# arksigner1.net
KiCad netlist of a schematic drawn in Altium Designer
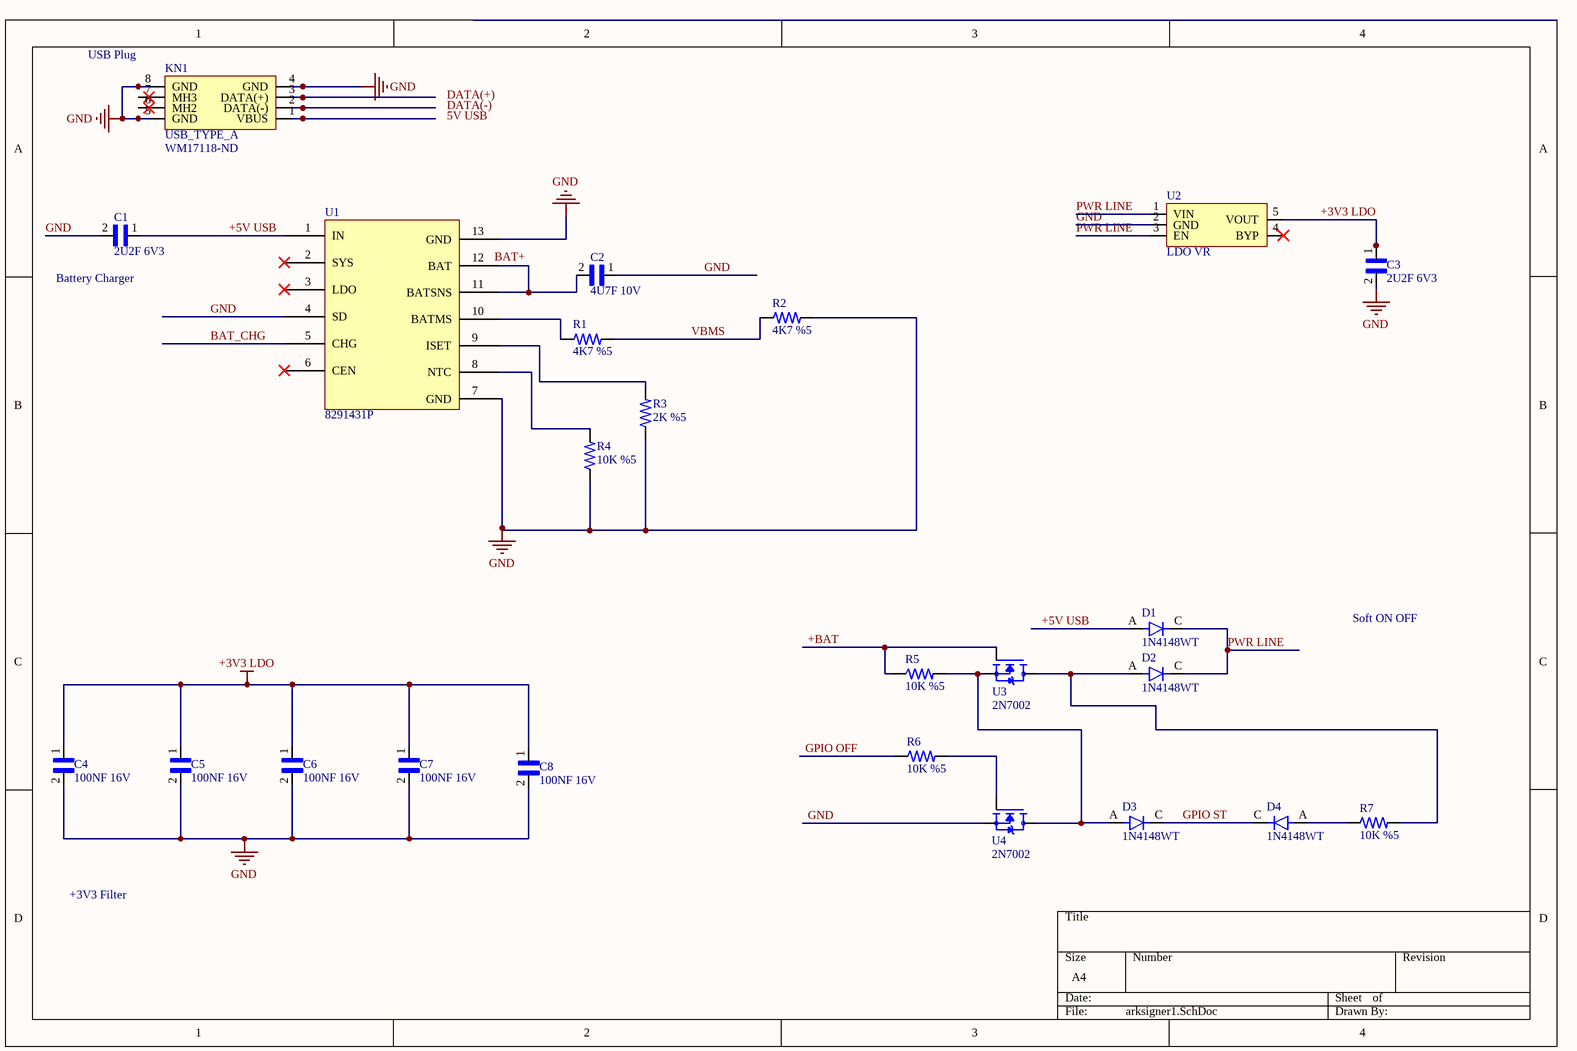
[diagram p0: arksigner1.SchDoc]

(export (version "E")
  (design (tool "Eeschema 10.0.6"))
  (components
    (comp (ref "C1")
      (value "2U2F 6V3")
      (footprint "CAP")
      (fields (field (name "MP") "06035J6R8BBSTR"))
      (libsource (lib "") (part "06035J6R8BBSTR_1"))
    )
    (comp (ref "C2")
      (value "4U7F 10V")
      (footprint "CAP")
      (fields (field (name "MP") "06035J6R8BBSTR"))
      (libsource (lib "") (part "06035J6R8BBSTR_1"))
    )
    (comp (ref "C3")
      (value "2U2F 6V3")
      (footprint "CAP")
      (fields (field (name "MP") "06035J6R8BBSTR"))
      (libsource (lib "Soft_Latch_11082021") (part "06035J6R8BBSTR"))
    )
    (comp (ref "C4")
      (value "100NF 16V")
      (footprint "CAP")
      (fields (field (name "MP") "06035J6R8BBSTR"))
      (libsource (lib "Soft_Latch_11082021") (part "06035J6R8BBSTR"))
    )
    (comp (ref "C5")
      (value "100NF 16V")
      (footprint "CAP")
      (fields (field (name "MP") "06035J6R8BBSTR"))
      (libsource (lib "Soft_Latch_11082021") (part "06035J6R8BBSTR"))
    )
    (comp (ref "C6")
      (value "100NF 16V")
      (footprint "CAP")
      (fields (field (name "MP") "06035J6R8BBSTR"))
      (libsource (lib "Soft_Latch_11082021") (part "06035J6R8BBSTR"))
    )
    (comp (ref "C7")
      (value "100NF 16V")
      (footprint "CAP")
      (fields (field (name "MP") "06035J6R8BBSTR"))
      (libsource (lib "Soft_Latch_11082021") (part "06035J6R8BBSTR"))
    )
    (comp (ref "C8")
      (value "100NF 16V")
      (footprint "CAP")
      (fields (field (name "MP") "06035J6R8BBSTR"))
      (libsource (lib "Soft_Latch_11082021") (part "06035J6R8BBSTR"))
    )
    (comp (ref "D1")
      (value "1N4148WT")
      (footprint "SnapEDApcb:SODFL1608X70N")
      (description "Diode Standard 100V 150mA Surface Mount SOD-123")
      (fields (field (name "MP") "1N4148W+") (field (name "MF") "Micro Commercial"))
      (libsource (lib "Soft_Latch_11082021") (part "1N4148WT"))
    )
    (comp (ref "D2")
      (value "1N4148WT")
      (footprint "SnapEDApcb:SODFL1608X70N")
      (description "Diode Standard 100V 150mA Surface Mount SOD-123")
      (fields (field (name "MP") "1N4148W+") (field (name "MF") "Micro Commercial"))
      (libsource (lib "Soft_Latch_11082021") (part "1N4148WT"))
    )
    (comp (ref "D3")
      (value "1N4148WT")
      (footprint "SnapEDApcb:SODFL1608X70N")
      (description "Diode Standard 100V 150mA Surface Mount SOD-123")
      (fields (field (name "MP") "1N4148W+") (field (name "MF") "Micro Commercial"))
      (libsource (lib "Soft_Latch_11082021") (part "1N4148WT"))
    )
    (comp (ref "D4")
      (value "1N4148WT")
      (footprint "SnapEDApcb:SODFL1608X70N")
      (description "Diode Standard 100V 150mA Surface Mount SOD-123")
      (fields (field (name "MP") "1N4148W+") (field (name "MF") "Micro Commercial"))
      (libsource (lib "Soft_Latch_11082021") (part "1N4148WT"))
    )
    (comp (ref "KN1")
      (value "USB_TYPE_A")
      (description "Conn USB 2.0 Type A PL 4 POS Solder RA SMD 4 Terminal 1 Port Tray")
      (fields
        (field (name "MANUFACTURER") "Molex")
        (field (name "MANUFACTURER PART NUMBER") "0480371000")
        (field (name "SUPPLIER PART NUMBER 1") "WM17118-ND")
      )
      (libsource (lib "Soft_Latch_11082021") (part "USB_TYPE_A"))
    )
    (comp (ref "R1")
      (value "4K7 %5")
      (footprint "RES")
      (description "RES SMD 22K OHM 0.1% 1/16W 0603")
      (fields (field (name "MF") "TE Connectivity") (field (name "MP") "8-1676481-3"))
      (libsource (lib "Soft_Latch_11082021") (part "8-1676481-3"))
    )
    (comp (ref "R2")
      (value "4K7 %5")
      (footprint "RES")
      (description "RES SMD 22K OHM 0.1% 1/16W 0603")
      (fields (field (name "MF") "TE Connectivity") (field (name "MP") "8-1676481-3"))
      (libsource (lib "Soft_Latch_11082021") (part "8-1676481-3"))
    )
    (comp (ref "R3")
      (value "2K %5")
      (footprint "RES")
      (description "RES SMD 22K OHM 0.1% 1/16W 0603")
      (fields (field (name "MF") "TE Connectivity") (field (name "MP") "8-1676481-3"))
      (libsource (lib "Soft_Latch_11082021") (part "8-1676481-3"))
    )
    (comp (ref "R4")
      (value "10K %5")
      (footprint "RES")
      (description "RES SMD 22K OHM 0.1% 1/16W 0603")
      (fields (field (name "MF") "TE Connectivity") (field (name "MP") "8-1676481-3"))
      (libsource (lib "Soft_Latch_11082021") (part "8-1676481-3"))
    )
    (comp (ref "R5")
      (value "10K %5")
      (footprint "RES")
      (description "RES SMD 22K OHM 0.1% 1/16W 0603")
      (fields (field (name "MF") "TE Connectivity") (field (name "MP") "8-1676481-3"))
      (libsource (lib "Soft_Latch_11082021") (part "8-1676481-3"))
    )
    (comp (ref "R6")
      (value "10K %5")
      (footprint "RES")
      (description "RES SMD 22K OHM 0.1% 1/16W 0603")
      (fields (field (name "MF") "TE Connectivity") (field (name "MP") "8-1676481-3"))
      (libsource (lib "Soft_Latch_11082021") (part "8-1676481-3"))
    )
    (comp (ref "R7")
      (value "10K %5")
      (footprint "RES")
      (description "RES SMD 22K OHM 0.1% 1/16W 0603")
      (fields (field (name "MF") "TE Connectivity") (field (name "MP") "8-1676481-3"))
      (libsource (lib "Soft_Latch_11082021") (part "8-1676481-3"))
    )
    (comp (ref "U1")
      (value "STNS01")
      (description "IC LI-ION BATT CHARGER LDO 12DFN")
      (fields
        (field (name "MANUFACTURER") "STMicroelectronics")
        (field (name "MANUFACTURER PART NUMBER") "STNS01PUR")
        (field (name "SUPPLIER PART NUMBER 1") "8291431P")
      )
      (libsource (lib "arksigner1") (part "STNS01"))
    )
    (comp (ref "U2")
      (value "LDO VR")
      (description "IC REG LDO 3.3V 0.15A SOT23-5")
      (fields
        (field (name "MANUFACTURER") "Microchip")
        (field (name "MANUFACTURER PART NUMBER") "MIC5205-3.3BM5TR")
      )
      (libsource (lib "arksigner1") (part "LDO VR"))
    )
    (comp (ref "U3")
      (value "2N7002")
      (footprint "SOT95P240X111-3N:SOT95P240X111-3N")
      (description "N-Channel 60V 280mA (Ta) 350mW (Ta) Surface Mount SOT-23-3 (TO-236)")
      (fields (field (name "MF") "ON Semiconductor"))
      (libsource (lib "Soft_Latch_11082021") (part "2N7002"))
    )
    (comp (ref "U4")
      (value "2N7002")
      (footprint "SOT95P240X111-3N:SOT95P240X111-3N")
      (description "N-Channel 60V 280mA (Ta) 350mW (Ta) Surface Mount SOT-23-3 (TO-236)")
      (fields (field (name "MF") "ON Semiconductor"))
      (libsource (lib "Soft_Latch_11082021") (part "2N7002"))
    )
  )
  (nets
    (net (code "1") (name "+3V3 LDO") (class "Default")
      (node (ref "C3") (pin "1") (pinfunction "1_1") (pintype "passive"))
      (node (ref "C4") (pin "1") (pinfunction "1_1") (pintype "passive"))
      (node (ref "C5") (pin "1") (pinfunction "1_1") (pintype "passive"))
      (node (ref "C6") (pin "1") (pinfunction "1_1") (pintype "passive"))
      (node (ref "C7") (pin "1") (pinfunction "1_1") (pintype "passive"))
      (node (ref "C8") (pin "1") (pinfunction "1_1") (pintype "passive"))
      (node (ref "U2") (pin "5") (pinfunction "VOUT_5") (pintype "passive"))
    )
    (net (code "2") (name "/+5V USB") (class "Default")
      (node (ref "C1") (pin "1") (pinfunction "1_1") (pintype "passive"))
      (node (ref "D1") (pin "A") (pinfunction "A_A") (pintype "passive"))
      (node (ref "U1") (pin "1") (pinfunction "IN_1") (pintype "passive"))
    )
    (net (code "3") (name "/+BAT") (class "Default")
      (node (ref "R5") (pin "1") (pinfunction "1_1") (pintype "passive"))
      (node (ref "U3") (pin "1") (pinfunction "G_1") (pintype "passive"))
    )
    (net (code "6") (name "/BAT_CHG") (class "Default")
      (node (ref "U1") (pin "5") (pinfunction "CHG_5") (pintype "passive"))
    )
    (net (code "9") (name "/GPIO OFF") (class "Default")
      (node (ref "R6") (pin "1") (pinfunction "1_1") (pintype "passive"))
    )
    (net (code "10") (name "/GPIO ST") (class "Default")
      (node (ref "D3") (pin "C") (pinfunction "C_C") (pintype "passive"))
      (node (ref "D4") (pin "C") (pinfunction "C_C") (pintype "passive"))
    )
    (net (code "11") (name "/PWR LINE") (class "Default")
      (node (ref "D1") (pin "C") (pinfunction "C_C") (pintype "passive"))
      (node (ref "D2") (pin "C") (pinfunction "C_C") (pintype "passive"))
      (node (ref "U2") (pin "1") (pinfunction "VIN_1") (pintype "passive"))
      (node (ref "U2") (pin "3") (pinfunction "EN_3") (pintype "passive"))
    )
    (net (code "12") (name "/VBMS") (class "Default")
      (node (ref "R1") (pin "2") (pinfunction "2_2") (pintype "passive"))
      (node (ref "R2") (pin "1") (pinfunction "1_1") (pintype "passive"))
    )
    (net (code "13") (name "GND") (class "Default")
      (node (ref "C1") (pin "2") (pinfunction "2_2") (pintype "passive"))
      (node (ref "C2") (pin "1") (pinfunction "1_1") (pintype "passive"))
      (node (ref "C3") (pin "2") (pinfunction "2_2") (pintype "passive"))
      (node (ref "C4") (pin "2") (pinfunction "2_2") (pintype "passive"))
      (node (ref "C5") (pin "2") (pinfunction "2_2") (pintype "passive"))
      (node (ref "C6") (pin "2") (pinfunction "2_2") (pintype "passive"))
      (node (ref "C7") (pin "2") (pinfunction "2_2") (pintype "passive"))
      (node (ref "C8") (pin "2") (pinfunction "2_2") (pintype "passive"))
      (node (ref "KN1") (pin "4") (pinfunction "GND_4") (pintype "passive"))
      (node (ref "KN1") (pin "5") (pinfunction "GND_5") (pintype "passive"))
      (node (ref "KN1") (pin "8") (pinfunction "GND_8") (pintype "passive"))
      (node (ref "R2") (pin "2") (pinfunction "2_2") (pintype "passive"))
      (node (ref "R3") (pin "1") (pinfunction "1_1") (pintype "passive"))
      (node (ref "R4") (pin "1") (pinfunction "1_1") (pintype "passive"))
      (node (ref "U1") (pin "13") (pinfunction "GND_13") (pintype "passive"))
      (node (ref "U1") (pin "4") (pinfunction "SD_4") (pintype "passive"))
      (node (ref "U1") (pin "7") (pinfunction "GND_7") (pintype "passive"))
      (node (ref "U2") (pin "2") (pinfunction "GND_2") (pintype "passive"))
      (node (ref "U4") (pin "2") (pinfunction "S_2") (pintype "passive"))
    )
    (net (code "14") (name "Net-(D4-PadA)") (class "Default")
      (node (ref "D4") (pin "A") (pinfunction "A_A") (pintype "passive"))
      (node (ref "R7") (pin "1") (pinfunction "1_1") (pintype "passive"))
    )
    (net (code "15") (name "Net-(U1-BAT)") (class "Default")
      (node (ref "C2") (pin "2") (pinfunction "2_2") (pintype "passive"))
      (node (ref "U1") (pin "11") (pinfunction "BATSNS_11") (pintype "passive"))
      (node (ref "U1") (pin "12") (pinfunction "BAT_12") (pintype "passive"))
    )
    (net (code "16") (name "Net-(U1-BATMS)") (class "Default")
      (node (ref "R1") (pin "1") (pinfunction "1_1") (pintype "passive"))
      (node (ref "U1") (pin "10") (pinfunction "BATMS_10") (pintype "passive"))
    )
    (net (code "17") (name "Net-(U1-ISET)") (class "Default")
      (node (ref "R3") (pin "2") (pinfunction "2_2") (pintype "passive"))
      (node (ref "U1") (pin "9") (pinfunction "ISET_9") (pintype "passive"))
    )
    (net (code "18") (name "Net-(U1-NTC)") (class "Default")
      (node (ref "R4") (pin "2") (pinfunction "2_2") (pintype "passive"))
      (node (ref "U1") (pin "8") (pinfunction "NTC_8") (pintype "passive"))
    )
    (net (code "19") (name "Net-(U3-D)") (class "Default")
      (node (ref "D2") (pin "A") (pinfunction "A_A") (pintype "passive"))
      (node (ref "R7") (pin "2") (pinfunction "2_2") (pintype "passive"))
      (node (ref "U3") (pin "3") (pinfunction "D_3") (pintype "passive"))
    )
    (net (code "20") (name "Net-(U3-S)") (class "Default")
      (node (ref "D3") (pin "A") (pinfunction "A_A") (pintype "passive"))
      (node (ref "R5") (pin "2") (pinfunction "2_2") (pintype "passive"))
      (node (ref "U3") (pin "2") (pinfunction "S_2") (pintype "passive"))
      (node (ref "U4") (pin "3") (pinfunction "D_3") (pintype "passive"))
    )
    (net (code "21") (name "Net-(U4-G)") (class "Default")
      (node (ref "R6") (pin "2") (pinfunction "2_2") (pintype "passive"))
      (node (ref "U4") (pin "1") (pinfunction "G_1") (pintype "passive"))
    )
    (net (code "22") (name "unconnected-(KN1-DATA(+)-Pad3)") (class "Default")
      (node (ref "KN1") (pin "3") (pinfunction "DATA(+)_3") (pintype "passive"))
    )
    (net (code "23") (name "unconnected-(KN1-DATA(-)-Pad2)") (class "Default")
      (node (ref "KN1") (pin "2") (pinfunction "DATA(-)_2") (pintype "passive"))
    )
    (net (code "24") (name "unconnected-(KN1-MH2-Pad6)") (class "Default")
      (node (ref "KN1") (pin "6") (pinfunction "MH2_6") (pintype "passive"))
    )
    (net (code "25") (name "unconnected-(KN1-MH3-Pad7)") (class "Default")
      (node (ref "KN1") (pin "7") (pinfunction "MH3_7") (pintype "passive"))
    )
    (net (code "26") (name "unconnected-(KN1-VBUS-Pad1)") (class "Default")
      (node (ref "KN1") (pin "1") (pinfunction "VBUS_1") (pintype "passive"))
    )
    (net (code "27") (name "unconnected-(U1-CEN-Pad6)") (class "Default")
      (node (ref "U1") (pin "6") (pinfunction "CEN_6") (pintype "passive+no_connect"))
    )
    (net (code "28") (name "unconnected-(U1-LDO-Pad3)") (class "Default")
      (node (ref "U1") (pin "3") (pinfunction "LDO_3") (pintype "passive+no_connect"))
    )
    (net (code "29") (name "unconnected-(U1-SYS-Pad2)") (class "Default")
      (node (ref "U1") (pin "2") (pinfunction "SYS_2") (pintype "passive+no_connect"))
    )
    (net (code "30") (name "unconnected-(U2-BYP-Pad4)") (class "Default")
      (node (ref "U2") (pin "4") (pinfunction "BYP_4") (pintype "passive+no_connect"))
    )
  )
)
